# 1-5.net
KiCad netlist of a schematic drawn in EAGLE
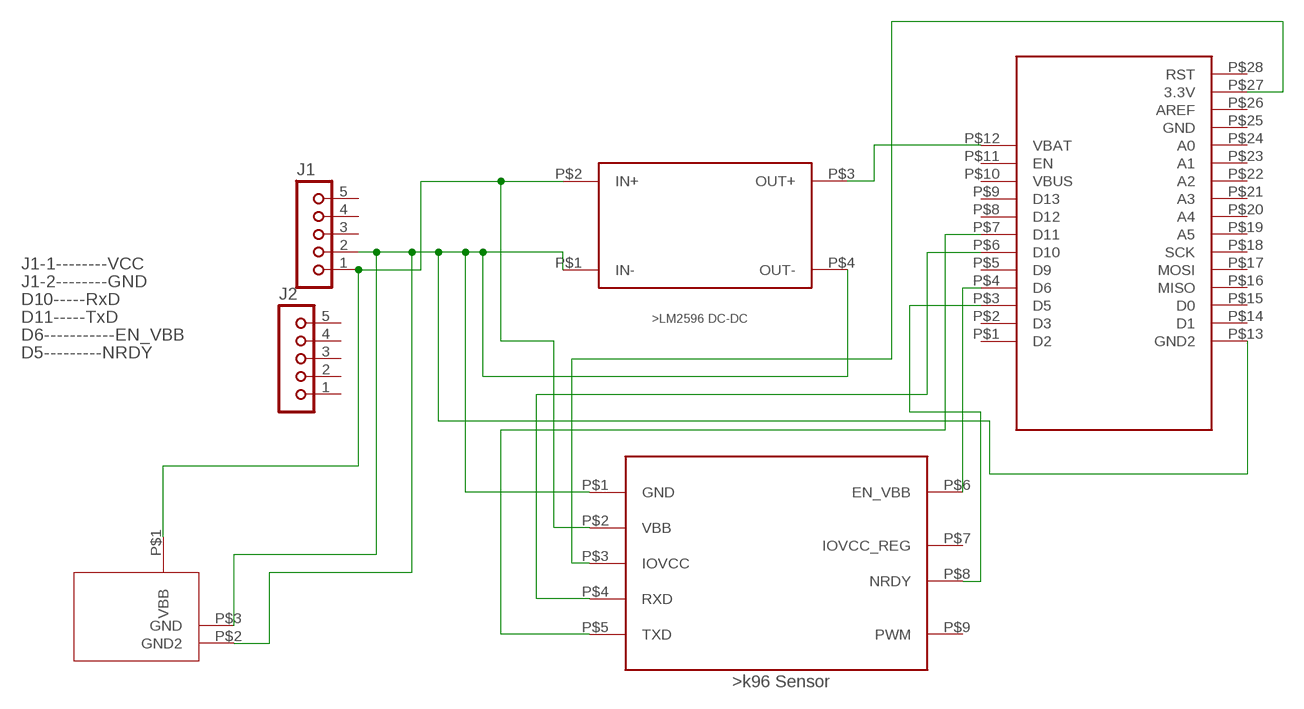
[diagram p0: schematic, sheet 1]

(export (version "E")
  (design (tool "Eeschema 10.0.6"))
  (components
    (comp (ref "DCDC1")
      (value "DCDC")
      (footprint "eagle-import:DCDC")
      (libsource (lib "eagle-import") (part "DCDC"))
    )
    (comp (ref "FEATHER1")
      (value "FEATHER")
      (footprint "eagle-import:FEATHER")
      (libsource (lib "eagle-import") (part "FEATHER"))
    )
    (comp (ref "J1")
      (value "JU05")
      (footprint "eagle-import:JU05")
      (libsource (lib "eagle-import") (part "JU05"))
    )
    (comp (ref "J2")
      (value "JU05")
      (footprint "eagle-import:JU05")
      (libsource (lib "eagle-import") (part "JU05"))
    )
    (comp (ref "K96SENSOR1")
      (value "K96SENSOR")
      (footprint "eagle-import:K96SENSOR")
      (libsource (lib "eagle-import") (part "K96SENSOR"))
    )
    (comp (ref "U$1")
      (value "POWER")
      (footprint "eagle-import:POWERIN")
      (libsource (lib "eagle-import") (part "POWER"))
    )
  )
  (nets
    (net (code "1") (name "Net-(DCDC1-IN+)") (class "Default")
      (node (ref "DCDC1") (pin "P$2") (pinfunction "IN+_P$2") (pintype "bidirectional"))
      (node (ref "J1") (pin "1") (pinfunction "1_1") (pintype "passive"))
      (node (ref "K96SENSOR1") (pin "P$2") (pinfunction "VBB_P$2") (pintype "bidirectional"))
      (node (ref "U$1") (pin "P$1") (pinfunction "VBB_P$1") (pintype "bidirectional"))
    )
    (net (code "2") (name "Net-(DCDC1-IN-)") (class "Default")
      (node (ref "DCDC1") (pin "P$1") (pinfunction "IN-_P$1") (pintype "bidirectional"))
      (node (ref "DCDC1") (pin "P$4") (pinfunction "OUT-_P$4") (pintype "bidirectional"))
      (node (ref "FEATHER1") (pin "P$13") (pinfunction "GND2_P$13") (pintype "bidirectional"))
      (node (ref "J1") (pin "2") (pinfunction "2_2") (pintype "passive"))
      (node (ref "K96SENSOR1") (pin "P$1") (pinfunction "GND_P$1") (pintype "bidirectional"))
      (node (ref "U$1") (pin "P$2") (pinfunction "GND2_P$2") (pintype "bidirectional"))
      (node (ref "U$1") (pin "P$3") (pinfunction "GND_P$3") (pintype "bidirectional"))
    )
    (net (code "3") (name "Net-(DCDC1-OUT+)") (class "Default")
      (node (ref "DCDC1") (pin "P$3") (pinfunction "OUT+_P$3") (pintype "bidirectional"))
      (node (ref "FEATHER1") (pin "P$12") (pinfunction "VBAT_P$12") (pintype "bidirectional"))
    )
    (net (code "4") (name "Net-(FEATHER1-3.3V)") (class "Default")
      (node (ref "FEATHER1") (pin "P$27") (pinfunction "3.3V_P$27") (pintype "bidirectional"))
      (node (ref "K96SENSOR1") (pin "P$3") (pinfunction "IOVCC_P$3") (pintype "bidirectional"))
    )
    (net (code "5") (name "Net-(FEATHER1-D5)") (class "Default")
      (node (ref "FEATHER1") (pin "P$3") (pinfunction "D5_P$3") (pintype "bidirectional"))
      (node (ref "K96SENSOR1") (pin "P$8") (pinfunction "NRDY_P$8") (pintype "bidirectional"))
    )
    (net (code "6") (name "Net-(FEATHER1-D6)") (class "Default")
      (node (ref "FEATHER1") (pin "P$4") (pinfunction "D6_P$4") (pintype "bidirectional"))
      (node (ref "K96SENSOR1") (pin "P$6") (pinfunction "EN_VBB_P$6") (pintype "bidirectional"))
    )
    (net (code "7") (name "Net-(FEATHER1-D10)") (class "Default")
      (node (ref "FEATHER1") (pin "P$6") (pinfunction "D10_P$6") (pintype "bidirectional"))
      (node (ref "K96SENSOR1") (pin "P$4") (pinfunction "RXD_P$4") (pintype "bidirectional"))
    )
    (net (code "8") (name "Net-(FEATHER1-D11)") (class "Default")
      (node (ref "FEATHER1") (pin "P$7") (pinfunction "D11_P$7") (pintype "bidirectional"))
      (node (ref "K96SENSOR1") (pin "P$5") (pinfunction "TXD_P$5") (pintype "bidirectional"))
    )
    (net (code "9") (name "unconnected-(FEATHER1-A0-PadP$24)") (class "Default")
      (node (ref "FEATHER1") (pin "P$24") (pinfunction "A0_P$24") (pintype "bidirectional"))
    )
    (net (code "10") (name "unconnected-(FEATHER1-A1-PadP$23)") (class "Default")
      (node (ref "FEATHER1") (pin "P$23") (pinfunction "A1_P$23") (pintype "bidirectional"))
    )
    (net (code "11") (name "unconnected-(FEATHER1-A2-PadP$22)") (class "Default")
      (node (ref "FEATHER1") (pin "P$22") (pinfunction "A2_P$22") (pintype "bidirectional"))
    )
    (net (code "12") (name "unconnected-(FEATHER1-A3-PadP$21)") (class "Default")
      (node (ref "FEATHER1") (pin "P$21") (pinfunction "A3_P$21") (pintype "bidirectional"))
    )
    (net (code "13") (name "unconnected-(FEATHER1-A4-PadP$20)") (class "Default")
      (node (ref "FEATHER1") (pin "P$20") (pinfunction "A4_P$20") (pintype "bidirectional"))
    )
    (net (code "14") (name "unconnected-(FEATHER1-A5-PadP$19)") (class "Default")
      (node (ref "FEATHER1") (pin "P$19") (pinfunction "A5_P$19") (pintype "bidirectional"))
    )
    (net (code "15") (name "unconnected-(FEATHER1-AREF-PadP$26)") (class "Default")
      (node (ref "FEATHER1") (pin "P$26") (pinfunction "AREF_P$26") (pintype "bidirectional"))
    )
    (net (code "16") (name "unconnected-(FEATHER1-D0-PadP$15)") (class "Default")
      (node (ref "FEATHER1") (pin "P$15") (pinfunction "D0_P$15") (pintype "bidirectional"))
    )
    (net (code "17") (name "unconnected-(FEATHER1-D1-PadP$14)") (class "Default")
      (node (ref "FEATHER1") (pin "P$14") (pinfunction "D1_P$14") (pintype "bidirectional"))
    )
    (net (code "18") (name "unconnected-(FEATHER1-D2-PadP$1)") (class "Default")
      (node (ref "FEATHER1") (pin "P$1") (pinfunction "D2_P$1") (pintype "bidirectional"))
    )
    (net (code "19") (name "unconnected-(FEATHER1-D3-PadP$2)") (class "Default")
      (node (ref "FEATHER1") (pin "P$2") (pinfunction "D3_P$2") (pintype "bidirectional"))
    )
    (net (code "20") (name "unconnected-(FEATHER1-D9-PadP$5)") (class "Default")
      (node (ref "FEATHER1") (pin "P$5") (pinfunction "D9_P$5") (pintype "bidirectional"))
    )
    (net (code "21") (name "unconnected-(FEATHER1-D12-PadP$8)") (class "Default")
      (node (ref "FEATHER1") (pin "P$8") (pinfunction "D12_P$8") (pintype "bidirectional"))
    )
    (net (code "22") (name "unconnected-(FEATHER1-D13-PadP$9)") (class "Default")
      (node (ref "FEATHER1") (pin "P$9") (pinfunction "D13_P$9") (pintype "bidirectional"))
    )
    (net (code "23") (name "unconnected-(FEATHER1-EN-PadP$11)") (class "Default")
      (node (ref "FEATHER1") (pin "P$11") (pinfunction "EN_P$11") (pintype "bidirectional"))
    )
    (net (code "24") (name "unconnected-(FEATHER1-GND-PadP$25)") (class "Default")
      (node (ref "FEATHER1") (pin "P$25") (pinfunction "GND_P$25") (pintype "bidirectional"))
    )
    (net (code "25") (name "unconnected-(FEATHER1-MISO-PadP$16)") (class "Default")
      (node (ref "FEATHER1") (pin "P$16") (pinfunction "MISO_P$16") (pintype "bidirectional"))
    )
    (net (code "26") (name "unconnected-(FEATHER1-MOSI-PadP$17)") (class "Default")
      (node (ref "FEATHER1") (pin "P$17") (pinfunction "MOSI_P$17") (pintype "bidirectional"))
    )
    (net (code "27") (name "unconnected-(FEATHER1-RST-PadP$28)") (class "Default")
      (node (ref "FEATHER1") (pin "P$28") (pinfunction "RST_P$28") (pintype "bidirectional"))
    )
    (net (code "28") (name "unconnected-(FEATHER1-SCK-PadP$18)") (class "Default")
      (node (ref "FEATHER1") (pin "P$18") (pinfunction "SCK_P$18") (pintype "bidirectional"))
    )
    (net (code "29") (name "unconnected-(FEATHER1-VBUS-PadP$10)") (class "Default")
      (node (ref "FEATHER1") (pin "P$10") (pinfunction "VBUS_P$10") (pintype "bidirectional"))
    )
    (net (code "30") (name "unconnected-(J1-Pad3)") (class "Default")
      (node (ref "J1") (pin "3") (pinfunction "3_3") (pintype "passive"))
    )
    (net (code "31") (name "unconnected-(J1-Pad4)") (class "Default")
      (node (ref "J1") (pin "4") (pinfunction "4_4") (pintype "passive"))
    )
    (net (code "32") (name "unconnected-(J1-Pad5)") (class "Default")
      (node (ref "J1") (pin "5") (pinfunction "5_5") (pintype "passive"))
    )
    (net (code "33") (name "unconnected-(J2-Pad1)") (class "Default")
      (node (ref "J2") (pin "1") (pinfunction "1_1") (pintype "passive"))
    )
    (net (code "34") (name "unconnected-(J2-Pad2)") (class "Default")
      (node (ref "J2") (pin "2") (pinfunction "2_2") (pintype "passive"))
    )
    (net (code "35") (name "unconnected-(J2-Pad3)") (class "Default")
      (node (ref "J2") (pin "3") (pinfunction "3_3") (pintype "passive"))
    )
    (net (code "36") (name "unconnected-(J2-Pad4)") (class "Default")
      (node (ref "J2") (pin "4") (pinfunction "4_4") (pintype "passive"))
    )
    (net (code "37") (name "unconnected-(J2-Pad5)") (class "Default")
      (node (ref "J2") (pin "5") (pinfunction "5_5") (pintype "passive"))
    )
    (net (code "38") (name "unconnected-(K96SENSOR1-IOVCC_REG-PadP$7)") (class "Default")
      (node (ref "K96SENSOR1") (pin "P$7") (pinfunction "IOVCC_REG_P$7") (pintype "bidirectional"))
    )
    (net (code "39") (name "unconnected-(K96SENSOR1-PWM-PadP$9)") (class "Default")
      (node (ref "K96SENSOR1") (pin "P$9") (pinfunction "PWM_P$9") (pintype "bidirectional"))
    )
  )
)
